# 04C-001A.net
KiCad netlist of a schematic drawn in EAGLE
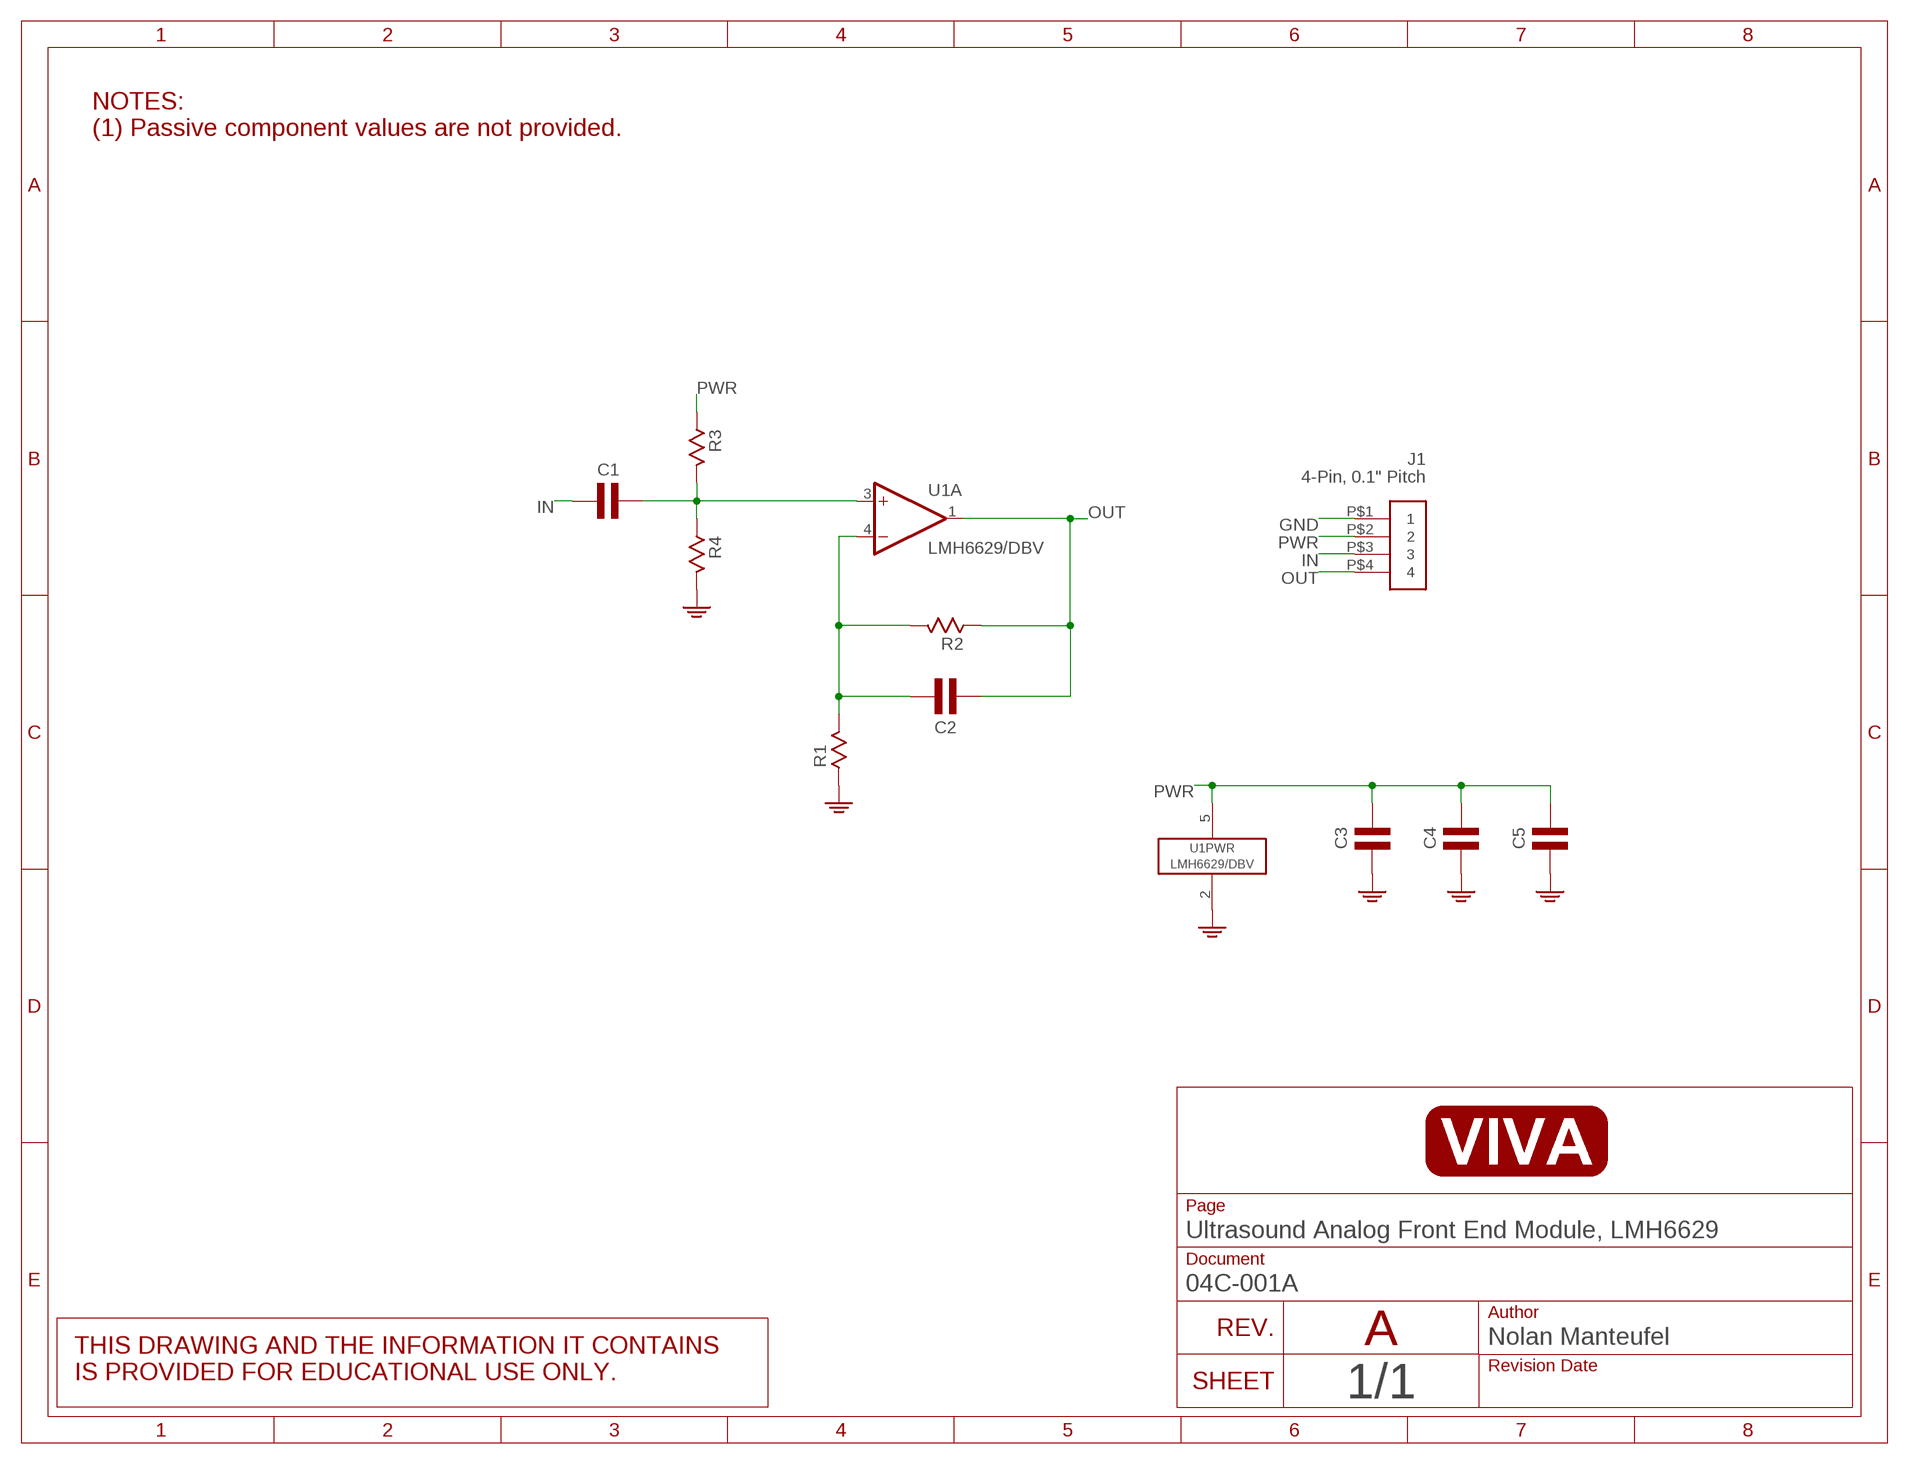
[diagram p0: schematic, sheet 1]

(export (version "E")
  (design (tool "Eeschema 10.0.6"))
  (components
    (comp (ref "C1")
      (value "C0805")
      (footprint "eagle-import:C0805")
      (libsource (lib "eagle-import") (part "C0805"))
    )
    (comp (ref "C2")
      (value "C0805")
      (footprint "eagle-import:C0805")
      (libsource (lib "eagle-import") (part "C0805"))
    )
    (comp (ref "C3")
      (value "C0805")
      (footprint "eagle-import:C0805")
      (libsource (lib "eagle-import") (part "C0805"))
    )
    (comp (ref "C4")
      (value "C0805")
      (footprint "eagle-import:C0805")
      (libsource (lib "eagle-import") (part "C0805"))
    )
    (comp (ref "C5")
      (value "C0805")
      (footprint "eagle-import:C0805")
      (libsource (lib "eagle-import") (part "C0805"))
    )
    (comp (ref "J1")
      (value "4-Pin, 0.1\" Pitch")
      (footprint "eagle-import:PCB_4")
      (libsource (lib "eagle-import") (part "PINS_4SILK"))
    )
    (comp (ref "R1")
      (value "R0805")
      (footprint "eagle-import:R0805")
      (libsource (lib "eagle-import") (part "R0805"))
    )
    (comp (ref "R2")
      (value "R0805")
      (footprint "eagle-import:R0805")
      (libsource (lib "eagle-import") (part "R0805"))
    )
    (comp (ref "R3")
      (value "R0805")
      (footprint "eagle-import:R0805")
      (libsource (lib "eagle-import") (part "R0805"))
    )
    (comp (ref "R4")
      (value "R0805")
      (footprint "eagle-import:R0805")
      (libsource (lib "eagle-import") (part "R0805"))
    )
    (comp (ref "U1")
      (value "LMH6629/DBV")
      (footprint "eagle-import:SOT23-5")
      (libsource (lib "eagle-import") (part "LMH6629/DBV"))
    )
  )
  (nets
    (net (code "1") (name "/IN") (class "Default")
      (node (ref "C1") (pin "1") (pinfunction "P$1_1") (pintype "passive"))
      (node (ref "J1") (pin "P$3") (pinfunction "3_P$3") (pintype "bidirectional"))
    )
    (net (code "2") (name "/OUT") (class "Default")
      (node (ref "C2") (pin "1") (pinfunction "P$1_1") (pintype "passive"))
      (node (ref "J1") (pin "P$4") (pinfunction "4_P$4") (pintype "bidirectional"))
      (node (ref "R2") (pin "1") (pinfunction "P$1_1") (pintype "bidirectional"))
      (node (ref "U1") (pin "1") (pinfunction "OUT_1") (pintype "output"))
    )
    (net (code "3") (name "/PWR") (class "Default")
      (node (ref "C3") (pin "2") (pinfunction "P$2_2") (pintype "passive"))
      (node (ref "C4") (pin "2") (pinfunction "P$2_2") (pintype "passive"))
      (node (ref "C5") (pin "2") (pinfunction "P$2_2") (pintype "passive"))
      (node (ref "J1") (pin "P$2") (pinfunction "2_P$2") (pintype "bidirectional"))
      (node (ref "R3") (pin "1") (pinfunction "P$1_1") (pintype "bidirectional"))
      (node (ref "U1") (pin "5") (pinfunction "V+_5") (pintype "power_in"))
    )
    (net (code "4") (name "GND") (class "Default")
      (node (ref "C3") (pin "1") (pinfunction "P$1_1") (pintype "passive"))
      (node (ref "C4") (pin "1") (pinfunction "P$1_1") (pintype "passive"))
      (node (ref "C5") (pin "1") (pinfunction "P$1_1") (pintype "passive"))
      (node (ref "J1") (pin "P$1") (pinfunction "1_P$1") (pintype "bidirectional"))
      (node (ref "R1") (pin "1") (pinfunction "P$1_1") (pintype "bidirectional"))
      (node (ref "R4") (pin "2") (pinfunction "P$2_2") (pintype "bidirectional"))
      (node (ref "U1") (pin "2") (pinfunction "V-_2") (pintype "power_in"))
    )
    (net (code "5") (name "Net-(C1-P$2)") (class "Default")
      (node (ref "C1") (pin "2") (pinfunction "P$2_2") (pintype "passive"))
      (node (ref "R3") (pin "2") (pinfunction "P$2_2") (pintype "bidirectional"))
      (node (ref "R4") (pin "1") (pinfunction "P$1_1") (pintype "bidirectional"))
      (node (ref "U1") (pin "3") (pinfunction "+IN_3") (pintype "input"))
    )
    (net (code "6") (name "Net-(C2-P$2)") (class "Default")
      (node (ref "C2") (pin "2") (pinfunction "P$2_2") (pintype "passive"))
      (node (ref "R1") (pin "2") (pinfunction "P$2_2") (pintype "bidirectional"))
      (node (ref "R2") (pin "2") (pinfunction "P$2_2") (pintype "bidirectional"))
      (node (ref "U1") (pin "4") (pinfunction "-IN_4") (pintype "input"))
    )
  )
)
